# DCS_MCU.net
KiCad netlist of a schematic drawn in Altium Designer
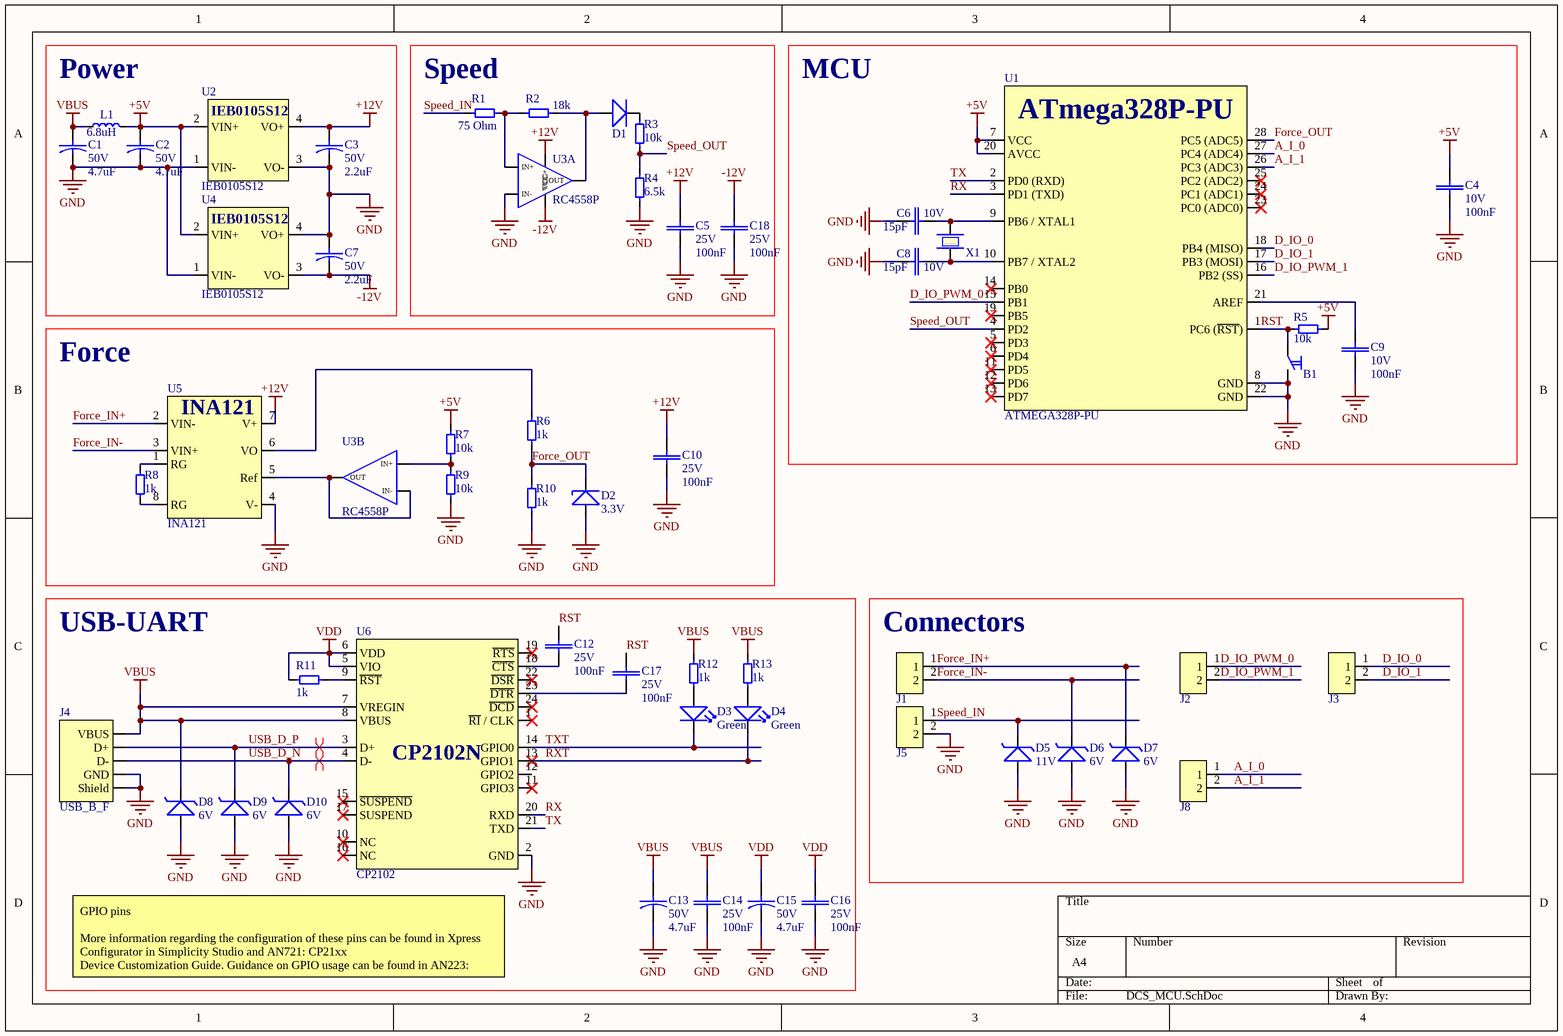
[diagram p0: DCS_MCU.SchDoc]

(export (version "E")
  (design (tool "Eeschema 10.0.6"))
  (components
    (comp (ref "B1")
      (value "Button_SPST")
      (footprint "Button_small")
      (libsource (lib "Symbols") (part "Button_SPST_NO"))
    )
    (comp (ref "C1")
      (value "4.7uF")
      (footprint "CAPPRD200W50D400H800")
      (fields (field (name "VOLTAGE") "50V") (field (name "Comment") "Capacitor_NP"))
      (libsource (lib "Symbols") (part "Capacitor_P"))
    )
    (comp (ref "C2")
      (value "4.7uF")
      (footprint "CAPPRD200W50D400H800")
      (fields (field (name "VOLTAGE") "50V") (field (name "Comment") "Capacitor_NP"))
      (libsource (lib "Symbols") (part "Capacitor_P"))
    )
    (comp (ref "C3")
      (value "2.2uF")
      (footprint "CAPPRD200W50D400H800")
      (fields (field (name "VOLTAGE") "50V") (field (name "Comment") "Capacitor_NP"))
      (libsource (lib "Symbols") (part "Capacitor_P"))
    )
    (comp (ref "C4")
      (value "100nF")
      (footprint "CAPRD500W50D400H600")
      (fields (field (name "VOLTAGE") "10V") (field (name "Comment") "Capacitor_NP"))
      (libsource (lib "Symbols") (part "Capacitor_NP"))
    )
    (comp (ref "C5")
      (value "100nF")
      (footprint "CAPRD500W50D400H600")
      (fields (field (name "VOLTAGE") "25V") (field (name "Comment") "Capacitor_NP"))
      (libsource (lib "Symbols") (part "Capacitor_NP"))
    )
    (comp (ref "C6")
      (value "15pF")
      (footprint "CAPRD500W50D400H600")
      (fields (field (name "VOLTAGE") "10V") (field (name "Comment") "Capacitor_NP"))
      (libsource (lib "Symbols") (part "Capacitor_NP"))
    )
    (comp (ref "C7")
      (value "2.2uF")
      (footprint "CAPPRD200W50D400H800")
      (fields (field (name "VOLTAGE") "50V") (field (name "Comment") "Capacitor_NP"))
      (libsource (lib "Symbols") (part "Capacitor_P"))
    )
    (comp (ref "C8")
      (value "15pF")
      (footprint "CAPRD500W50D400H600")
      (fields (field (name "VOLTAGE") "10V") (field (name "Comment") "Capacitor_NP"))
      (libsource (lib "Symbols") (part "Capacitor_NP"))
    )
    (comp (ref "C9")
      (value "100nF")
      (footprint "CAPRD500W50D400H600")
      (fields (field (name "VOLTAGE") "10V") (field (name "Comment") "Capacitor_NP"))
      (libsource (lib "Symbols") (part "Capacitor_NP"))
    )
    (comp (ref "C10")
      (value "100nF")
      (footprint "CAPRD500W50D400H600")
      (fields (field (name "VOLTAGE") "25V") (field (name "Comment") "Capacitor_NP"))
      (libsource (lib "Symbols") (part "Capacitor_NP"))
    )
    (comp (ref "C12")
      (value "100nF")
      (footprint "CAPRD500W50D400H600")
      (fields (field (name "VOLTAGE") "25V") (field (name "Comment") "Capacitor_NP"))
      (libsource (lib "Symbols") (part "Capacitor_NP"))
    )
    (comp (ref "C13")
      (value "4.7uF")
      (footprint "CAPPRD200W50D400H800")
      (fields (field (name "VOLTAGE") "50V") (field (name "Comment") "Capacitor_NP"))
      (libsource (lib "Symbols") (part "Capacitor_P"))
    )
    (comp (ref "C14")
      (value "100nF")
      (footprint "CAPRD500W50D400H600")
      (fields (field (name "VOLTAGE") "25V") (field (name "Comment") "Capacitor_NP"))
      (libsource (lib "Symbols") (part "Capacitor_NP"))
    )
    (comp (ref "C15")
      (value "4.7uF")
      (footprint "CAPPRD200W50D400H800")
      (fields (field (name "VOLTAGE") "50V") (field (name "Comment") "Capacitor_NP"))
      (libsource (lib "Symbols") (part "Capacitor_P"))
    )
    (comp (ref "C16")
      (value "100nF")
      (footprint "CAPRD500W50D400H600")
      (fields (field (name "VOLTAGE") "25V") (field (name "Comment") "Capacitor_NP"))
      (libsource (lib "Symbols") (part "Capacitor_NP"))
    )
    (comp (ref "C17")
      (value "100nF")
      (footprint "CAPRD500W50D400H600")
      (fields (field (name "VOLTAGE") "25V") (field (name "Comment") "Capacitor_NP"))
      (libsource (lib "Symbols") (part "Capacitor_NP"))
    )
    (comp (ref "C18")
      (value "100nF")
      (footprint "CAPRD500W50D400H600")
      (fields (field (name "VOLTAGE") "25V") (field (name "Comment") "Capacitor_NP"))
      (libsource (lib "Symbols") (part "Capacitor_NP"))
    )
    (comp (ref "D1")
      (value "Diode")
      (footprint "DIOAD450W35L350D200")
      (libsource (lib "Symbols") (part "Diode_Rectifier"))
    )
    (comp (ref "D2")
      (value "Diode_Zener")
      (footprint "DIOAD450W35L350D200")
      (fields (field (name "VOLTAGE") "3.3V"))
      (libsource (lib "Symbols") (part "Diode_Zener"))
    )
    (comp (ref "D3")
      (value "Diode_LED")
      (footprint "LEDRD254W60D600H1000")
      (fields (field (name "COLOR") "Green"))
      (libsource (lib "Symbols") (part "Diode_LED"))
    )
    (comp (ref "D4")
      (value "Diode_LED")
      (footprint "LEDRD254W60D600H1000")
      (fields (field (name "COLOR") "Green"))
      (libsource (lib "Symbols") (part "Diode_LED"))
    )
    (comp (ref "D5")
      (value "Diode_TVS")
      (footprint "DIOAD450W35L350D200")
      (fields (field (name "VOLTAGE") "11V"))
      (libsource (lib "Symbols") (part "Diode_TVS"))
    )
    (comp (ref "D6")
      (value "Diode_TVS")
      (footprint "DIOAD450W35L350D200")
      (fields (field (name "VOLTAGE") "6V"))
      (libsource (lib "Symbols") (part "Diode_TVS"))
    )
    (comp (ref "D7")
      (value "Diode_TVS")
      (footprint "DIOAD450W35L350D200")
      (fields (field (name "VOLTAGE") "6V"))
      (libsource (lib "Symbols") (part "Diode_TVS"))
    )
    (comp (ref "D8")
      (value "Diode_TVS")
      (footprint "DIOAD450W35L350D200")
      (fields (field (name "VOLTAGE") "6V"))
      (libsource (lib "Symbols") (part "Diode_TVS"))
    )
    (comp (ref "D9")
      (value "Diode_TVS")
      (footprint "DIOAD450W35L350D200")
      (fields (field (name "VOLTAGE") "6V"))
      (libsource (lib "Symbols") (part "Diode_TVS"))
    )
    (comp (ref "D10")
      (value "Diode_TVS")
      (footprint "DIOAD450W35L350D200")
      (fields (field (name "VOLTAGE") "6V"))
      (libsource (lib "Symbols") (part "Diode_TVS"))
    )
    (comp (ref "J1")
      (value "Terminal_2-pole")
      (footprint "Terminal_2-pole")
      (libsource (lib "Symbols") (part "Terminal_2-pole"))
    )
    (comp (ref "J2")
      (value "Terminal_2-pole")
      (footprint "Terminal_2-pole")
      (libsource (lib "Symbols") (part "Terminal_2-pole"))
    )
    (comp (ref "J3")
      (value "Terminal_2-pole")
      (footprint "Terminal_2-pole")
      (libsource (lib "Symbols") (part "Terminal_2-pole"))
    )
    (comp (ref "J4") (value "USB_B_F") (footprint "USB_B_F") (libsource (lib "Symbols") (part "USB_B_F")))
    (comp (ref "J5")
      (value "Terminal_2-pole")
      (footprint "Terminal_2-pole")
      (libsource (lib "Symbols") (part "Terminal_2-pole"))
    )
    (comp (ref "J8")
      (value "Terminal_2-pole")
      (footprint "Terminal_2-pole")
      (libsource (lib "Symbols") (part "Terminal_2-pole"))
    )
    (comp (ref "L1")
      (value "6.8uH")
      (footprint "INDRD360W60D650H1000")
      (fields (field (name "Comment") "Inductor"))
      (libsource (lib "Symbols") (part "Inductor"))
    )
    (comp (ref "R1")
      (value "75 Ohm")
      (footprint "RESAD710W60L610D260")
      (fields (field (name "Comment") "Resistor"))
      (libsource (lib "") (part "Resistor_1"))
    )
    (comp (ref "R2")
      (value "18k")
      (footprint "RESAD710W60L610D260")
      (fields (field (name "Comment") "Resistor"))
      (libsource (lib "") (part "Resistor_1"))
    )
    (comp (ref "R3")
      (value "10k")
      (footprint "RESAD710W60L610D260")
      (fields (field (name "Comment") "Resistor"))
      (libsource (lib "Symbols") (part "Resistor"))
    )
    (comp (ref "R4")
      (value "6.5k")
      (footprint "RESAD710W60L610D260")
      (fields (field (name "Comment") "Resistor"))
      (libsource (lib "Symbols") (part "Resistor"))
    )
    (comp (ref "R5")
      (value "10k")
      (footprint "RESAD710W60L610D260")
      (fields (field (name "Comment") "Resistor"))
      (libsource (lib "") (part "Resistor_2"))
    )
    (comp (ref "R6")
      (value "1k")
      (footprint "RESAD710W60L610D260")
      (fields (field (name "Comment") "Resistor"))
      (libsource (lib "Symbols") (part "Resistor"))
    )
    (comp (ref "R7")
      (value "10k")
      (footprint "RESAD710W60L610D260")
      (fields (field (name "Comment") "Resistor"))
      (libsource (lib "Symbols") (part "Resistor"))
    )
    (comp (ref "R8")
      (value "1k")
      (footprint "RESAD710W60L610D260")
      (fields (field (name "Comment") "Resistor"))
      (libsource (lib "Symbols") (part "Resistor"))
    )
    (comp (ref "R9")
      (value "10k")
      (footprint "RESAD710W60L610D260")
      (fields (field (name "Comment") "Resistor"))
      (libsource (lib "Symbols") (part "Resistor"))
    )
    (comp (ref "R10")
      (value "1k")
      (footprint "RESAD710W60L610D260")
      (fields (field (name "Comment") "Resistor"))
      (libsource (lib "Symbols") (part "Resistor"))
    )
    (comp (ref "R11")
      (value "1k")
      (footprint "RESAD710W60L610D260")
      (fields (field (name "Comment") "Resistor"))
      (libsource (lib "") (part "Resistor_1"))
    )
    (comp (ref "R12")
      (value "1k")
      (footprint "RESAD710W60L610D260")
      (fields (field (name "Comment") "Resistor"))
      (libsource (lib "Symbols") (part "Resistor"))
    )
    (comp (ref "R13")
      (value "1k")
      (footprint "RESAD710W60L610D260")
      (fields (field (name "Comment") "Resistor"))
      (libsource (lib "Symbols") (part "Resistor"))
    )
    (comp (ref "U1")
      (value "ATMEGA328P-PU")
      (footprint "DIP790W46P254L3556H508Q28")
      (libsource (lib "Symbols") (part "ATMEGA328P-PU"))
    )
    (comp (ref "U2")
      (value "IEB0105S12")
      (footprint "SIP600W50P254L1160H1016Q4")
      (libsource (lib "Symbols") (part "IEB0105S12"))
    )
    (comp (ref "U3")
      (value "RC4558P")
      (footprint "DIP1092W45P254L1016H508Q8")
      (libsource (lib "Symbols") (part "RC4558P"))
    )
    (comp (ref "U4")
      (value "IEB0105S12")
      (footprint "SIP600W50P254L1160H1016Q4")
      (libsource (lib "Symbols") (part "IEB0105S12"))
    )
    (comp (ref "U5")
      (value "INA121")
      (footprint "DIP1092W45P254L1016H508Q8")
      (libsource (lib "Symbols") (part "INA121"))
    )
    (comp (ref "U6")
      (value "CP2102")
      (footprint "QFN25P50_400X400X80L40X24T245N")
      (libsource (lib "Symbols") (part "CP2102"))
    )
    (comp (ref "X1")
      (value "Oscillator")
      (footprint "XTAL_HC49P488T45L1150W380H350")
      (libsource (lib "Symbols") (part "Oscillator"))
    )
  )
  (nets
    (net (code "1") (name "+5V") (class "Default")
      (node (ref "C2") (pin "2") (pinfunction "2_2") (pintype "passive"))
      (node (ref "C4") (pin "2") (pinfunction "2_2") (pintype "passive"))
      (node (ref "L1") (pin "2") (pinfunction "2_2") (pintype "passive"))
      (node (ref "R5") (pin "1") (pinfunction "1_1") (pintype "passive"))
      (node (ref "R7") (pin "2") (pinfunction "2_2") (pintype "passive"))
      (node (ref "U1") (pin "20") (pinfunction "AVCC_20") (pintype "passive"))
      (node (ref "U1") (pin "7") (pinfunction "VCC_7") (pintype "passive"))
      (node (ref "U2") (pin "2") (pinfunction "VIN+_2") (pintype "passive"))
      (node (ref "U4") (pin "2") (pinfunction "VIN+_2") (pintype "passive"))
    )
    (net (code "2") (name "+12V") (class "Default")
      (node (ref "C10") (pin "2") (pinfunction "2_2") (pintype "passive"))
      (node (ref "C3") (pin "2") (pinfunction "2_2") (pintype "passive"))
      (node (ref "C5") (pin "2") (pinfunction "2_2") (pintype "passive"))
      (node (ref "U2") (pin "4") (pinfunction "VO+_4") (pintype "passive"))
      (node (ref "U3") (pin "8") (pinfunction "VCC+_8") (pintype "power_in"))
      (node (ref "U5") (pin "7") (pinfunction "V+_7") (pintype "passive"))
    )
    (net (code "3") (name "-12V") (class "Default")
      (node (ref "C18") (pin "2") (pinfunction "2_2") (pintype "passive"))
      (node (ref "C7") (pin "1") (pinfunction "1_1") (pintype "passive"))
      (node (ref "U3") (pin "4") (pinfunction "VCC-_4") (pintype "power_in"))
      (node (ref "U4") (pin "3") (pinfunction "VO-_3") (pintype "passive"))
    )
    (net (code "4") (name "/A_I_0") (class "Default")
      (node (ref "J8") (pin "1") (pinfunction "1_1") (pintype "passive"))
      (node (ref "U1") (pin "27") (pinfunction "PC4_(ADC4)_27") (pintype "passive"))
    )
    (net (code "5") (name "/A_I_1") (class "Default")
      (node (ref "J8") (pin "2") (pinfunction "2_2") (pintype "passive"))
      (node (ref "U1") (pin "26") (pinfunction "PC3_(ADC3)_26") (pintype "passive"))
    )
    (net (code "6") (name "/D_IO_0") (class "Default")
      (node (ref "J3") (pin "1") (pinfunction "1_1") (pintype "passive"))
      (node (ref "U1") (pin "18") (pinfunction "PB4_(MISO)_18") (pintype "passive"))
    )
    (net (code "7") (name "/D_IO_1") (class "Default")
      (node (ref "J3") (pin "2") (pinfunction "2_2") (pintype "passive"))
      (node (ref "U1") (pin "17") (pinfunction "PB3_(MOSI)_17") (pintype "passive"))
    )
    (net (code "8") (name "/D_IO_PWM_0") (class "Default")
      (node (ref "J2") (pin "1") (pinfunction "1_1") (pintype "passive"))
      (node (ref "U1") (pin "15") (pinfunction "PB1_15") (pintype "passive"))
    )
    (net (code "9") (name "/D_IO_PWM_1") (class "Default")
      (node (ref "J2") (pin "2") (pinfunction "2_2") (pintype "passive"))
      (node (ref "U1") (pin "16") (pinfunction "PB2_(SS)_16") (pintype "passive"))
    )
    (net (code "10") (name "/Force_IN+") (class "Default")
      (node (ref "D7") (pin "C") (pinfunction "C_C") (pintype "passive"))
      (node (ref "J1") (pin "1") (pinfunction "1_1") (pintype "passive"))
      (node (ref "U5") (pin "2") (pinfunction "VIN-_2") (pintype "passive"))
    )
    (net (code "11") (name "/Force_IN-") (class "Default")
      (node (ref "D6") (pin "C") (pinfunction "C_C") (pintype "passive"))
      (node (ref "J1") (pin "2") (pinfunction "2_2") (pintype "passive"))
      (node (ref "U5") (pin "3") (pinfunction "VIN+_3") (pintype "passive"))
    )
    (net (code "12") (name "/Force_OUT") (class "Default")
      (node (ref "D2") (pin "C") (pinfunction "C_C") (pintype "passive"))
      (node (ref "R10") (pin "2") (pinfunction "2_2") (pintype "passive"))
      (node (ref "R6") (pin "1") (pinfunction "1_1") (pintype "passive"))
      (node (ref "U1") (pin "28") (pinfunction "PC5_(ADC5)_28") (pintype "passive"))
    )
    (net (code "13") (name "/RST") (class "Default")
      (node (ref "B1") (pin "1") (pinfunction "1_1") (pintype "passive"))
      (node (ref "C12") (pin "1") (pinfunction "1_1") (pintype "passive"))
      (node (ref "C17") (pin "1") (pinfunction "1_1") (pintype "passive"))
      (node (ref "R5") (pin "2") (pinfunction "2_2") (pintype "passive"))
      (node (ref "U1") (pin "1") (pinfunction "PC6_(~{RST})_1") (pintype "passive"))
    )
    (net (code "14") (name "/RX") (class "Default")
      (node (ref "U1") (pin "3") (pinfunction "PD1_(TXD)_3") (pintype "passive"))
      (node (ref "U6") (pin "20") (pinfunction "RXD_20") (pintype "passive"))
    )
    (net (code "15") (name "/RXT") (class "Default")
      (node (ref "D4") (pin "C") (pinfunction "C_C") (pintype "passive"))
      (node (ref "U6") (pin "13") (pinfunction "GPIO1_13") (pintype "passive"))
    )
    (net (code "16") (name "/Speed_IN") (class "Default")
      (node (ref "D5") (pin "C") (pinfunction "C_C") (pintype "passive"))
      (node (ref "J5") (pin "1") (pinfunction "1_1") (pintype "passive"))
      (node (ref "R1") (pin "1") (pinfunction "1_1") (pintype "passive"))
    )
    (net (code "17") (name "/Speed_OUT") (class "Default")
      (node (ref "R3") (pin "1") (pinfunction "1_1") (pintype "passive"))
      (node (ref "R4") (pin "2") (pinfunction "2_2") (pintype "passive"))
      (node (ref "U1") (pin "4") (pinfunction "PD2_4") (pintype "passive"))
    )
    (net (code "18") (name "/TX") (class "Default")
      (node (ref "U1") (pin "2") (pinfunction "PD0_(RXD)_2") (pintype "passive"))
      (node (ref "U6") (pin "21") (pinfunction "TXD_21") (pintype "passive"))
    )
    (net (code "19") (name "/TXT") (class "Default")
      (node (ref "D3") (pin "C") (pinfunction "C_C") (pintype "passive"))
      (node (ref "U6") (pin "14") (pinfunction "GPIO0_14") (pintype "passive"))
    )
    (net (code "20") (name "/USB_D_N") (class "Default")
      (node (ref "D10") (pin "C") (pinfunction "C_C") (pintype "passive"))
      (node (ref "J4") (pin "1") (pinfunction "D-_1") (pintype "passive"))
      (node (ref "U6") (pin "4") (pinfunction "D-_4") (pintype "passive"))
    )
    (net (code "21") (name "/USB_D_P") (class "Default")
      (node (ref "D9") (pin "C") (pinfunction "C_C") (pintype "passive"))
      (node (ref "J4") (pin "3") (pinfunction "D+_3") (pintype "passive"))
      (node (ref "U6") (pin "3") (pinfunction "D+_3") (pintype "passive"))
    )
    (net (code "22") (name "GND") (class "Default")
      (node (ref "B1") (pin "2") (pinfunction "2_2") (pintype "passive"))
      (node (ref "C1") (pin "1") (pinfunction "1_1") (pintype "passive"))
      (node (ref "C10") (pin "1") (pinfunction "1_1") (pintype "passive"))
      (node (ref "C13") (pin "1") (pinfunction "1_1") (pintype "passive"))
      (node (ref "C14") (pin "1") (pinfunction "1_1") (pintype "passive"))
      (node (ref "C15") (pin "1") (pinfunction "1_1") (pintype "passive"))
      (node (ref "C16") (pin "1") (pinfunction "1_1") (pintype "passive"))
      (node (ref "C18") (pin "1") (pinfunction "1_1") (pintype "passive"))
      (node (ref "C2") (pin "1") (pinfunction "1_1") (pintype "passive"))
      (node (ref "C3") (pin "1") (pinfunction "1_1") (pintype "passive"))
      (node (ref "C4") (pin "1") (pinfunction "1_1") (pintype "passive"))
      (node (ref "C5") (pin "1") (pinfunction "1_1") (pintype "passive"))
      (node (ref "C6") (pin "2") (pinfunction "2_2") (pintype "passive"))
      (node (ref "C7") (pin "2") (pinfunction "2_2") (pintype "passive"))
      (node (ref "C8") (pin "2") (pinfunction "2_2") (pintype "passive"))
      (node (ref "C9") (pin "1") (pinfunction "1_1") (pintype "passive"))
      (node (ref "D10") (pin "A") (pinfunction "A_A") (pintype "passive"))
      (node (ref "D2") (pin "A") (pinfunction "A_A") (pintype "passive"))
      (node (ref "D5") (pin "A") (pinfunction "A_A") (pintype "passive"))
      (node (ref "D6") (pin "A") (pinfunction "A_A") (pintype "passive"))
      (node (ref "D7") (pin "A") (pinfunction "A_A") (pintype "passive"))
      (node (ref "D8") (pin "A") (pinfunction "A_A") (pintype "passive"))
      (node (ref "D9") (pin "A") (pinfunction "A_A") (pintype "passive"))
      (node (ref "J4") (pin "4") (pinfunction "GND_4") (pintype "passive"))
      (node (ref "J4") (pin "5") (pinfunction "Shield_5") (pintype "passive"))
      (node (ref "J5") (pin "2") (pinfunction "2_2") (pintype "passive"))
      (node (ref "R10") (pin "1") (pinfunction "1_1") (pintype "passive"))
      (node (ref "R4") (pin "1") (pinfunction "1_1") (pintype "passive"))
      (node (ref "R9") (pin "1") (pinfunction "1_1") (pintype "passive"))
      (node (ref "U1") (pin "22") (pinfunction "GND_22") (pintype "passive"))
      (node (ref "U1") (pin "8") (pinfunction "GND_8") (pintype "passive"))
      (node (ref "U2") (pin "1") (pinfunction "VIN-_1") (pintype "passive"))
      (node (ref "U2") (pin "3") (pinfunction "VO-_3") (pintype "passive"))
      (node (ref "U3") (pin "2") (pinfunction "IN-_2") (pintype "passive"))
      (node (ref "U4") (pin "1") (pinfunction "VIN-_1") (pintype "passive"))
      (node (ref "U4") (pin "4") (pinfunction "VO+_4") (pintype "passive"))
      (node (ref "U5") (pin "4") (pinfunction "V-_4") (pintype "passive"))
      (node (ref "U6") (pin "2") (pinfunction "GND_2") (pintype "passive"))
    )
    (net (code "23") (name "Net-(D1-PadC)") (class "Default")
      (node (ref "D1") (pin "C") (pinfunction "C_C") (pintype "passive"))
      (node (ref "R3") (pin "2") (pinfunction "2_2") (pintype "passive"))
    )
    (net (code "24") (name "Net-(D3-PadA)") (class "Default")
      (node (ref "D3") (pin "A") (pinfunction "A_A") (pintype "passive"))
      (node (ref "R12") (pin "1") (pinfunction "1_1") (pintype "passive"))
    )
    (net (code "25") (name "Net-(D4-PadA)") (class "Default")
      (node (ref "D4") (pin "A") (pinfunction "A_A") (pintype "passive"))
      (node (ref "R13") (pin "1") (pinfunction "1_1") (pintype "passive"))
    )
    (net (code "26") (name "Net-(R8-Pad1)") (class "Default")
      (node (ref "R8") (pin "1") (pinfunction "1_1") (pintype "passive"))
      (node (ref "U5") (pin "8") (pinfunction "RG_8") (pintype "passive"))
    )
    (net (code "27") (name "Net-(R8-Pad2)") (class "Default")
      (node (ref "R8") (pin "2") (pinfunction "2_2") (pintype "passive"))
      (node (ref "U5") (pin "1") (pinfunction "RG_1") (pintype "passive"))
    )
    (net (code "28") (name "Net-(U1-AREF)") (class "Default")
      (node (ref "C9") (pin "2") (pinfunction "2_2") (pintype "passive"))
      (node (ref "U1") (pin "21") (pinfunction "AREF_21") (pintype "passive"))
    )
    (net (code "29") (name "Net-(U1-PB6_{slash}_XTAL1)") (class "Default")
      (node (ref "C6") (pin "1") (pinfunction "1_1") (pintype "passive"))
      (node (ref "U1") (pin "9") (pinfunction "PB6_/_XTAL1_9") (pintype "passive"))
      (node (ref "X1") (pin "2") (pinfunction "2_2") (pintype "passive"))
    )
    (net (code "30") (name "Net-(U1-PB7_{slash}_XTAL2)") (class "Default")
      (node (ref "C8") (pin "1") (pinfunction "1_1") (pintype "passive"))
      (node (ref "U1") (pin "10") (pinfunction "PB7_/_XTAL2_10") (pintype "passive"))
      (node (ref "X1") (pin "1") (pinfunction "1_1") (pintype "passive"))
    )
    (net (code "31") (name "Net-(U3A-IN+)") (class "Default")
      (node (ref "R1") (pin "2") (pinfunction "2_2") (pintype "passive"))
      (node (ref "R2") (pin "1") (pinfunction "1_1") (pintype "passive"))
      (node (ref "U3") (pin "3") (pinfunction "IN+_3") (pintype "passive"))
    )
    (net (code "32") (name "Net-(U3A-OUT)") (class "Default")
      (node (ref "D1") (pin "A") (pinfunction "A_A") (pintype "passive"))
      (node (ref "R2") (pin "2") (pinfunction "2_2") (pintype "passive"))
      (node (ref "U3") (pin "1") (pinfunction "OUT_1") (pintype "passive"))
    )
    (net (code "33") (name "Net-(U3B-IN+)") (class "Default")
      (node (ref "R7") (pin "1") (pinfunction "1_1") (pintype "passive"))
      (node (ref "R9") (pin "2") (pinfunction "2_2") (pintype "passive"))
      (node (ref "U3") (pin "5") (pinfunction "IN+_5") (pintype "passive"))
    )
    (net (code "34") (name "Net-(U3B-IN-)") (class "Default")
      (node (ref "U3") (pin "6") (pinfunction "IN-_6") (pintype "passive"))
      (node (ref "U3") (pin "7") (pinfunction "OUT_7") (pintype "passive"))
      (node (ref "U5") (pin "5") (pinfunction "Ref_5") (pintype "passive"))
    )
    (net (code "35") (name "Net-(U5-VO)") (class "Default")
      (node (ref "R6") (pin "2") (pinfunction "2_2") (pintype "passive"))
      (node (ref "U5") (pin "6") (pinfunction "VO_6") (pintype "passive"))
    )
    (net (code "36") (name "Net-(U6-~{CTS})") (class "Default")
      (node (ref "C12") (pin "2") (pinfunction "2_2") (pintype "passive"))
      (node (ref "U6") (pin "18") (pinfunction "~{CTS}_18") (pintype "passive"))
    )
    (net (code "37") (name "Net-(U6-~{DTR})") (class "Default")
      (node (ref "C17") (pin "2") (pinfunction "2_2") (pintype "passive"))
      (node (ref "U6") (pin "23") (pinfunction "~{DTR}_23") (pintype "passive"))
    )
    (net (code "38") (name "Net-(U6-~{RST})") (class "Default")
      (node (ref "R11") (pin "2") (pinfunction "2_2") (pintype "passive"))
      (node (ref "U6") (pin "9") (pinfunction "~{RST}_9") (pintype "passive"))
    )
    (net (code "39") (name "VBUS") (class "Default")
      (node (ref "C1") (pin "2") (pinfunction "2_2") (pintype "passive"))
      (node (ref "C13") (pin "2") (pinfunction "2_2") (pintype "passive"))
      (node (ref "C14") (pin "2") (pinfunction "2_2") (pintype "passive"))
      (node (ref "D8") (pin "C") (pinfunction "C_C") (pintype "passive"))
      (node (ref "J4") (pin "2") (pinfunction "VBUS_2") (pintype "passive"))
      (node (ref "L1") (pin "1") (pinfunction "1_1") (pintype "passive"))
      (node (ref "R12") (pin "2") (pinfunction "2_2") (pintype "passive"))
      (node (ref "R13") (pin "2") (pinfunction "2_2") (pintype "passive"))
      (node (ref "U6") (pin "7") (pinfunction "VREGIN_7") (pintype "passive"))
      (node (ref "U6") (pin "8") (pinfunction "VBUS_8") (pintype "passive"))
    )
    (net (code "40") (name "VDD") (class "Default")
      (node (ref "C15") (pin "2") (pinfunction "2_2") (pintype "passive"))
      (node (ref "C16") (pin "2") (pinfunction "2_2") (pintype "passive"))
      (node (ref "R11") (pin "1") (pinfunction "1_1") (pintype "passive"))
      (node (ref "U6") (pin "5") (pinfunction "VIO_5") (pintype "passive"))
      (node (ref "U6") (pin "6") (pinfunction "VDD_6") (pintype "passive"))
    )
    (net (code "41") (name "unconnected-(U1-PB0-Pad14)") (class "Default")
      (node (ref "U1") (pin "14") (pinfunction "PB0_14") (pintype "passive+no_connect"))
    )
    (net (code "42") (name "unconnected-(U1-PB5-Pad19)") (class "Default")
      (node (ref "U1") (pin "19") (pinfunction "PB5_19") (pintype "passive+no_connect"))
    )
    (net (code "43") (name "unconnected-(U1-PC0_(ADC0)-Pad23)") (class "Default")
      (node (ref "U1") (pin "23") (pinfunction "PC0_(ADC0)_23") (pintype "passive+no_connect"))
    )
    (net (code "44") (name "unconnected-(U1-PC1_(ADC1)-Pad24)") (class "Default")
      (node (ref "U1") (pin "24") (pinfunction "PC1_(ADC1)_24") (pintype "passive+no_connect"))
    )
    (net (code "45") (name "unconnected-(U1-PC2_(ADC2)-Pad25)") (class "Default")
      (node (ref "U1") (pin "25") (pinfunction "PC2_(ADC2)_25") (pintype "passive+no_connect"))
    )
    (net (code "46") (name "unconnected-(U1-PD3-Pad5)") (class "Default")
      (node (ref "U1") (pin "5") (pinfunction "PD3_5") (pintype "passive+no_connect"))
    )
    (net (code "47") (name "unconnected-(U1-PD4-Pad6)") (class "Default")
      (node (ref "U1") (pin "6") (pinfunction "PD4_6") (pintype "passive+no_connect"))
    )
    (net (code "48") (name "unconnected-(U1-PD5-Pad11)") (class "Default")
      (node (ref "U1") (pin "11") (pinfunction "PD5_11") (pintype "passive+no_connect"))
    )
    (net (code "49") (name "unconnected-(U1-PD6-Pad12)") (class "Default")
      (node (ref "U1") (pin "12") (pinfunction "PD6_12") (pintype "passive+no_connect"))
    )
    (net (code "50") (name "unconnected-(U1-PD7-Pad13)") (class "Default")
      (node (ref "U1") (pin "13") (pinfunction "PD7_13") (pintype "passive+no_connect"))
    )
    (net (code "51") (name "unconnected-(U6-GPIO2-Pad12)") (class "Default")
      (node (ref "U6") (pin "12") (pinfunction "GPIO2_12") (pintype "passive"))
    )
    (net (code "52") (name "unconnected-(U6-GPIO3-Pad11)") (class "Default")
      (node (ref "U6") (pin "11") (pinfunction "GPIO3_11") (pintype "passive+no_connect"))
    )
    (net (code "53") (name "unconnected-(U6-NC-Pad10)") (class "Default")
      (node (ref "U6") (pin "10") (pinfunction "NC_10") (pintype "passive+no_connect"))
    )
    (net (code "54") (name "unconnected-(U6-NC-Pad16)") (class "Default")
      (node (ref "U6") (pin "16") (pinfunction "NC_16") (pintype "passive+no_connect"))
    )
    (net (code "55") (name "unconnected-(U6-SUSPEND-Pad17)") (class "Default")
      (node (ref "U6") (pin "17") (pinfunction "SUSPEND_17") (pintype "passive+no_connect"))
    )
    (net (code "56") (name "unconnected-(U6-~{DCD}-Pad24)") (class "Default")
      (node (ref "U6") (pin "24") (pinfunction "~{DCD}_24") (pintype "passive+no_connect"))
    )
    (net (code "57") (name "unconnected-(U6-~{DSR}-Pad22)") (class "Default")
      (node (ref "U6") (pin "22") (pinfunction "~{DSR}_22") (pintype "passive+no_connect"))
    )
    (net (code "58") (name "unconnected-(U6-~{RI}_{slash}_CLK-Pad1)") (class "Default")
      (node (ref "U6") (pin "1") (pinfunction "~{RI}_/_CLK_1") (pintype "passive+no_connect"))
    )
    (net (code "59") (name "unconnected-(U6-~{RTS}-Pad19)") (class "Default")
      (node (ref "U6") (pin "19") (pinfunction "~{RTS}_19") (pintype "passive+no_connect"))
    )
    (net (code "60") (name "unconnected-(U6-~{SUSPEND}-Pad15)") (class "Default")
      (node (ref "U6") (pin "15") (pinfunction "~{SUSPEND}_15") (pintype "passive+no_connect"))
    )
  )
)
